# Sheet2.net
KiCad netlist of a schematic drawn in Altium Designer
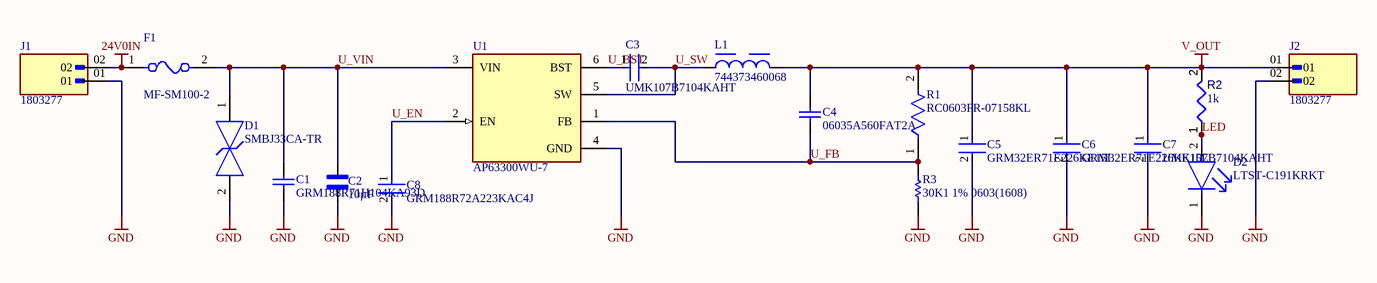
[diagram p0: Sheet2.SchDoc]

(export (version "E")
  (design (tool "Eeschema 10.0.6"))
  (components
    (comp (ref "C1")
      (value "GRM188R71H104KA93D")
      (footprint "CAPC1608X90X35ML10T15")
      (description "Chip Capacitor, 0.1 uF, +/- 10%, 50 V, -55 to 125 degC, 0603 (1608 Metric), RoHS, Tape and Reel")
      (fields (field (name "TOLERANCE") "10%") (field (name "VOLTAGE") "50V"))
      (libsource (lib "Altium Content Vault") (part "CAP-NP-2"))
    )
    (comp (ref "C2")
      (value "10µF")
      (footprint "CAPC3216X180N")
      (description "SMD capacitor X7R(EIA) with capacitance 10uF Tol.10%. Rated voltage 25Vdc 125C")
      (fields (field (name "MP") "GRM31CR71E106KA12L") (field (name "MF") "Murata Electronics"))
      (libsource (lib "HK") (part "GRM31CR71E106KA12L"))
    )
    (comp (ref "C3")
      (value "UMK107B7104KAHT")
      (footprint "FP-0603-L_1_6_0_1-W_0_8_0-IPC_B")
      (description "None")
      (fields (field (name "TOLERANCE") "10%"))
      (libsource (lib "Altium Content Vault") (part "02cd4be3c70576c341d710602a673aa"))
    )
    (comp (ref "C4")
      (value "06035A560FAT2A")
      (footprint "CAPC1608X90X35NL15T15")
      (fields (field (name "MANUFACTURER") "AVX Interconnect / Elco"))
      (libsource (lib "Altium Content Vault") (part "CAP"))
    )
    (comp (ref "C5")
      (value "GRM32ER71E226KE15L")
      (footprint "FP-GRM32E-0_3-0_2-MFG")
      (description "Chip Multilayer Ceramic Capacitors for General Purpose, 1210, 22uF, X7R, 15%, 10%, 25V")
      (fields (field (name "VOLTAGE") "25V") (field (name "TOLERANCE") "10%"))
      (libsource (lib "Altium Content Vault") (part "02cd4be3c70576c341d710602a673aa"))
    )
    (comp (ref "C6")
      (value "GRM32ER71E226KE15L")
      (footprint "FP-GRM32E-0_3-0_2-MFG")
      (description "Chip Multilayer Ceramic Capacitors for General Purpose, 1210, 22uF, X7R, 15%, 10%, 25V")
      (fields (field (name "VOLTAGE") "25V") (field (name "TOLERANCE") "10%"))
      (libsource (lib "Altium Content Vault") (part "02cd4be3c70576c341d710602a673aa"))
    )
    (comp (ref "C7")
      (value "UMK107B7104KAHT")
      (footprint "FP-0603-L_1_6_0_1-W_0_8_0-IPC_B")
      (description "None")
      (fields (field (name "TOLERANCE") "10%"))
      (libsource (lib "Altium Content Vault") (part "02cd4be3c70576c341d710602a673aa"))
    )
    (comp (ref "C8")
      (value "GRM188R72A223KAC4J")
      (footprint "FP-GRM188-0_1-e0_2_0_5-MFG")
      (description "Chip Multilayer Ceramic Capacitors for General Purpose, 0603, 22000pF, X7R, 15%, 10%, 100V")
      (fields (field (name "TOLERANCE") "10%"))
      (libsource (lib "Altium Content Vault") (part "11868f565c42a9108669ba33697ecf6"))
    )
    (comp (ref "D1")
      (value "SMBJ33CA-TR")
      (footprint "FP-SMB-CA-MFG")
      (description "TVS DIODE 33V 69.7V SMB")
      (fields
        (field (name "OCTOPART") "https://octopart.com/smbj33ca-tr-stmicroelectronics-347069")
        (field (name "MANUFACTURER") "STMicroelectronics")
      )
      (libsource (lib "Altium Content Vault") (part "11bd9d59d340f0612179daf16ad9b72"))
    )
    (comp (ref "D2")
      (value "LTST-C191KRKT")
      (footprint "FP-LTST-C191KRKT-MFG")
      (fields (field (name "VOLTAGE") "2V"))
      (libsource (lib "Altium Content Vault") (part "8706943c75ba83719d021d2fdc84c58"))
    )
    (comp (ref "F1")
      (value "MF-SM100-2")
      (footprint "FP-MF-SM100-2-MFG")
      (description "PTC RESET FUSE 30V 1.1A 2SMD")
      (fields
        (field (name "MANUFACTURER") "Bourns")
        (field (name "OCTOPART") "https://octopart.com/mf-sm100-2-bourns-125561")
      )
      (libsource (lib "Altium Content Vault") (part "5bcf9b9f640e542cf0359d10258e979"))
    )
    (comp (ref "J1")
      (value "1803277")
      (footprint "PHOENIX_1803277")
      (description "Pluggable Header 3.81mm 16AWG 160V 8A 2 Position COMBICON MC Series")
      (fields (field (name "MF") "Phoenix Contact"))
      (libsource (lib "") (part "1803277_1"))
    )
    (comp (ref "J2")
      (value "1803277")
      (footprint "PHOENIX_1803277")
      (description "Pluggable Header 3.81mm 16AWG 160V 8A 2 Position COMBICON MC Series")
      (fields (field (name "MF") "Phoenix Contact"))
      (libsource (lib "HK") (part "1803277"))
    )
    (comp (ref "L1")
      (value "744373460068")
      (footprint "WE-LHMI_7030")
      (fields (field (name "TOLERANCE") "20%"))
      (libsource (lib "Altium Content Vault") (part "Inductor - 3"))
    )
    (comp (ref "R1")
      (value "RC0603FR-07158KL")
      (footprint "FP-RC0603-0_55-MFG")
      (description "RES 158K OHM 1% 1/10W 0603")
      (fields (field (name "TOLERANCE") "1%"))
      (libsource (lib "Altium Content Vault") (part "1029c3af85768c4190bb7ad29bc67b5"))
    )
    (comp (ref "R2")
      (value "1k")
      (footprint "RESC1608X55X25ML10T15")
      (description "Chip Resistor, 1 KOhm, +/-1%, 0.1 W, -55 to 155 degC, 0603 (1608 Metric)")
      (fields (field (name "POWER") "100mW") (field (name "TOLERANCE") "1%"))
      (libsource (lib "HK") (part "RES-2"))
    )
    (comp (ref "R3")
      (value "30K1 1% 0603(1608)")
      (footprint "RESC0603(1608)_N")
      (description "30K1 0.1W 1% 0603 (1608 Metric)  SMD")
      (fields (field (name "TOLERANCE") "1 %") (field (name "POWER") "0.1 W"))
      (libsource (lib "Altium Content Vault") (part "RES"))
    )
    (comp (ref "U1")
      (value "AP63300WU-7")
      (footprint "FP-TSOT26-IPC_A")
      (description "DCDC CONV HV BUCK TSOT26")
      (libsource (lib "Altium Content Vault") (part "1f55634e5cdcb17378ea3938d0fe863"))
    )
  )
  (nets
    (net (code "1") (name "/LED") (class "Default")
      (node (ref "D2") (pin "2") (pinfunction "A_2") (pintype "passive"))
      (node (ref "R2") (pin "1") (pinfunction "1_1") (pintype "passive"))
    )
    (net (code "2") (name "/U_BST") (class "Default")
      (node (ref "C3") (pin "1") (pinfunction "1_1") (pintype "passive"))
      (node (ref "U1") (pin "6") (pinfunction "BST_6") (pintype "passive"))
    )
    (net (code "3") (name "/U_EN") (class "Default")
      (node (ref "C8") (pin "1") (pinfunction "1_1") (pintype "passive"))
      (node (ref "U1") (pin "2") (pinfunction "EN_2") (pintype "input"))
    )
    (net (code "4") (name "/U_FB") (class "Default")
      (node (ref "C4") (pin "1") (pinfunction "1_1") (pintype "passive"))
      (node (ref "R1") (pin "1") (pinfunction "1_1") (pintype "passive"))
      (node (ref "R3") (pin "2") (pinfunction "2_2") (pintype "passive"))
      (node (ref "U1") (pin "1") (pinfunction "FB_1") (pintype "passive"))
    )
    (net (code "5") (name "/U_SW") (class "Default")
      (node (ref "C3") (pin "2") (pinfunction "2_2") (pintype "passive"))
      (node (ref "L1") (pin "1") (pinfunction "1_1") (pintype "passive"))
      (node (ref "U1") (pin "5") (pinfunction "SW_5") (pintype "passive"))
    )
    (net (code "6") (name "/U_VIN") (class "Default")
      (node (ref "C1") (pin "2") (pinfunction "2_2") (pintype "passive"))
      (node (ref "C2") (pin "2") (pinfunction "2_2") (pintype "passive"))
      (node (ref "D1") (pin "1") (pinfunction "1_1") (pintype "passive"))
      (node (ref "F1") (pin "2") (pinfunction "2_2") (pintype "passive"))
      (node (ref "U1") (pin "3") (pinfunction "VIN_3") (pintype "power_in"))
    )
    (net (code "7") (name "24V0IN") (class "Default")
      (node (ref "F1") (pin "1") (pinfunction "1_1") (pintype "passive"))
      (node (ref "J1") (pin "02") (pinfunction "02_02") (pintype "passive"))
    )
    (net (code "8") (name "GND") (class "Default")
      (node (ref "C1") (pin "1") (pinfunction "1_1") (pintype "passive"))
      (node (ref "C2") (pin "1") (pinfunction "1_1") (pintype "passive"))
      (node (ref "C5") (pin "2") (pinfunction "2_2") (pintype "passive"))
      (node (ref "C6") (pin "2") (pinfunction "2_2") (pintype "passive"))
      (node (ref "C7") (pin "2") (pinfunction "2_2") (pintype "passive"))
      (node (ref "C8") (pin "2") (pinfunction "2_2") (pintype "passive"))
      (node (ref "D1") (pin "2") (pinfunction "2_2") (pintype "passive"))
      (node (ref "D2") (pin "1") (pinfunction "C_1") (pintype "passive"))
      (node (ref "J1") (pin "01") (pinfunction "01_01") (pintype "passive"))
      (node (ref "J2") (pin "02") (pinfunction "02_02") (pintype "passive"))
      (node (ref "R3") (pin "1") (pinfunction "1_1") (pintype "passive"))
      (node (ref "U1") (pin "4") (pinfunction "GND_4") (pintype "power_in"))
    )
    (net (code "9") (name "V_OUT") (class "Default")
      (node (ref "C4") (pin "2") (pinfunction "2_2") (pintype "passive"))
      (node (ref "C5") (pin "1") (pinfunction "1_1") (pintype "passive"))
      (node (ref "C6") (pin "1") (pinfunction "1_1") (pintype "passive"))
      (node (ref "C7") (pin "1") (pinfunction "1_1") (pintype "passive"))
      (node (ref "J2") (pin "01") (pinfunction "01_01") (pintype "passive"))
      (node (ref "L1") (pin "2") (pinfunction "2_2") (pintype "passive"))
      (node (ref "R1") (pin "2") (pinfunction "2_2") (pintype "passive"))
      (node (ref "R2") (pin "2") (pinfunction "2_2") (pintype "passive"))
    )
  )
)
